# Bidirectional_Voltage_Translator.net
KiCad netlist of a schematic drawn in Altium Designer
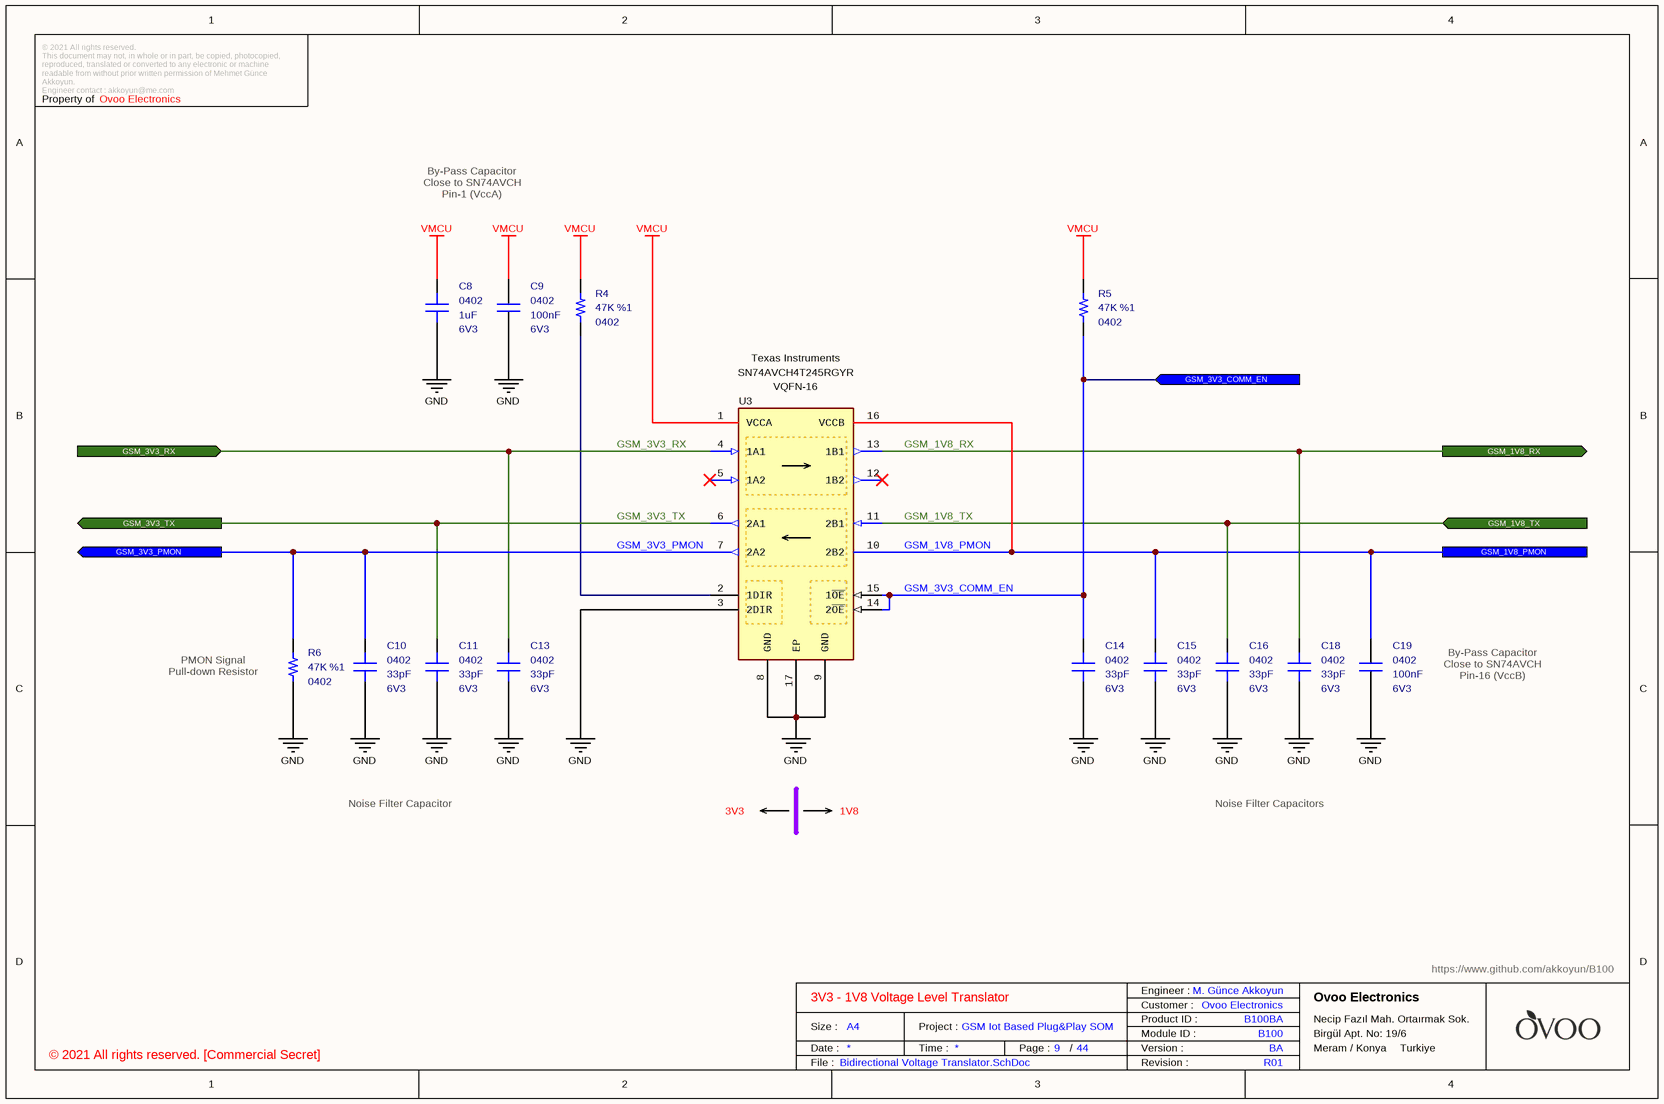
[diagram p0: Bidirectional Voltage Translator.SchDoc]

(export (version "E")
  (design (tool "Eeschema 10.0.6"))
  (components
    (comp (ref "C8")
      (value "1uF")
      (footprint "CAPACITOR_0402")
      (description "Capacitor - 1uF [0402] (Ceramic)")
      (fields
        (field (name "MANUFACTURER_PART_NUMBER") "GRM153R60J105ME95D")
        (field (name "MOUSER_PART_NUMBER") "81-GRM153R60J105ME5D")
        (field (name "CASE") "0402")
        (field (name "VOLTAGE") "6V3")
      )
      (libsource (lib "Ovoo_Schematic") (part "Capacitor - 1uF [0402-6V3)"))
    )
    (comp (ref "C9")
      (value "100nF")
      (footprint "CAPACITOR_0402")
      (description "Capacitor - 100nF [0402-6V3] (Ceramic)")
      (fields
        (field (name "MANUFACTURER_PART_NUMBER") "04026D104KAT4A")
        (field (name "MOUSER_PART_NUMBER") "581-04026D104KAT4A")
        (field (name "CASE") "0402")
        (field (name "VOLTAGE") "6V3")
      )
      (libsource (lib "Ovoo_Schematic") (part "Capacitor - 100nF [0402-6V3]"))
    )
    (comp (ref "C10")
      (value "33pF")
      (footprint "CAPACITOR_0402")
      (description "Capacitor - 33pF [0402] (Ceramic)")
      (fields
        (field (name "MANUFACTURER_PART_NUMBER") "C0402C330J9RACAUTO")
        (field (name "MOUSER_PART_NUMBER") "80-C0402C330J9RAUTO")
        (field (name "CASE") "0402")
        (field (name "VOLTAGE") "6V3")
      )
      (libsource (lib "Ovoo_Schematic") (part "Capacitor - 33pF [0402-6V3]"))
    )
    (comp (ref "C11")
      (value "33pF")
      (footprint "CAPACITOR_0402")
      (description "Capacitor - 33pF [0402] (Ceramic)")
      (fields
        (field (name "MANUFACTURER_PART_NUMBER") "C0402C330J9RACAUTO")
        (field (name "MOUSER_PART_NUMBER") "80-C0402C330J9RAUTO")
        (field (name "CASE") "0402")
        (field (name "VOLTAGE") "6V3")
      )
      (libsource (lib "Ovoo_Schematic") (part "Capacitor - 33pF [0402-6V3]"))
    )
    (comp (ref "C13")
      (value "33pF")
      (footprint "CAPACITOR_0402")
      (description "Capacitor - 33pF [0402] (Ceramic)")
      (fields
        (field (name "MANUFACTURER_PART_NUMBER") "C0402C330J9RACAUTO")
        (field (name "MOUSER_PART_NUMBER") "80-C0402C330J9RAUTO")
        (field (name "CASE") "0402")
        (field (name "VOLTAGE") "6V3")
      )
      (libsource (lib "Ovoo_Schematic") (part "Capacitor - 33pF [0402-6V3]"))
    )
    (comp (ref "C14")
      (value "33pF")
      (footprint "CAPACITOR_0402")
      (description "Capacitor - 33pF [0402] (Ceramic)")
      (fields
        (field (name "MANUFACTURER_PART_NUMBER") "C0402C330J9RACAUTO")
        (field (name "MOUSER_PART_NUMBER") "80-C0402C330J9RAUTO")
        (field (name "CASE") "0402")
        (field (name "VOLTAGE") "6V3")
      )
      (libsource (lib "Ovoo_Schematic") (part "Capacitor - 33pF [0402-6V3]"))
    )
    (comp (ref "C15")
      (value "33pF")
      (footprint "CAPACITOR_0402")
      (description "Capacitor - 33pF [0402] (Ceramic)")
      (fields
        (field (name "MANUFACTURER_PART_NUMBER") "C0402C330J9RACAUTO")
        (field (name "MOUSER_PART_NUMBER") "80-C0402C330J9RAUTO")
        (field (name "CASE") "0402")
        (field (name "VOLTAGE") "6V3")
      )
      (libsource (lib "Ovoo_Schematic") (part "Capacitor - 33pF [0402-6V3]"))
    )
    (comp (ref "C16")
      (value "33pF")
      (footprint "CAPACITOR_0402")
      (description "Capacitor - 33pF [0402] (Ceramic)")
      (fields
        (field (name "MANUFACTURER_PART_NUMBER") "C0402C330J9RACAUTO")
        (field (name "MOUSER_PART_NUMBER") "80-C0402C330J9RAUTO")
        (field (name "CASE") "0402")
        (field (name "VOLTAGE") "6V3")
      )
      (libsource (lib "Ovoo_Schematic") (part "Capacitor - 33pF [0402-6V3]"))
    )
    (comp (ref "C18")
      (value "33pF")
      (footprint "CAPACITOR_0402")
      (description "Capacitor - 33pF [0402] (Ceramic)")
      (fields
        (field (name "MANUFACTURER_PART_NUMBER") "C0402C330J9RACAUTO")
        (field (name "MOUSER_PART_NUMBER") "80-C0402C330J9RAUTO")
        (field (name "CASE") "0402")
        (field (name "VOLTAGE") "6V3")
      )
      (libsource (lib "Ovoo_Schematic") (part "Capacitor - 33pF [0402-6V3]"))
    )
    (comp (ref "C19")
      (value "100nF")
      (footprint "CAPACITOR_0402")
      (description "Capacitor - 100nF [0402-6V3] (Ceramic)")
      (fields
        (field (name "MANUFACTURER_PART_NUMBER") "04026D104KAT4A")
        (field (name "MOUSER_PART_NUMBER") "581-04026D104KAT4A")
        (field (name "CASE") "0402")
        (field (name "VOLTAGE") "6V3")
      )
      (libsource (lib "Ovoo_Schematic") (part "Capacitor - 100nF [0402-6V3]"))
    )
    (comp (ref "R4")
      (value "47K")
      (footprint "RESISTOR_0402")
      (description "Thick Film Resistors - SMD 1/16 W 47 Kohms 1%")
      (fields
        (field (name "MANUFACTURER_PART_NUMBER") "CRCW040247K0FKED")
        (field (name "MOUSER_PART_NUMBER") "71-CRCW0402-47K-E3")
        (field (name "TOLERANCE") "%1")
        (field (name "CASE") "0402")
      )
      (libsource (lib "Ovoo_Schematic") (part "Resistor - 47K"))
    )
    (comp (ref "R5")
      (value "47K")
      (footprint "RESISTOR_0402")
      (description "Thick Film Resistors - SMD 1/16 W 47 Kohms 1%")
      (fields
        (field (name "MANUFACTURER_PART_NUMBER") "CRCW040247K0FKED")
        (field (name "MOUSER_PART_NUMBER") "71-CRCW0402-47K-E3")
        (field (name "TOLERANCE") "%1")
        (field (name "CASE") "0402")
      )
      (libsource (lib "Ovoo_Schematic") (part "Resistor - 47K"))
    )
    (comp (ref "R6")
      (value "47K")
      (footprint "RESISTOR_0402")
      (description "Thick Film Resistors - SMD 1/16 W 47 Kohms 1%")
      (fields
        (field (name "MANUFACTURER_PART_NUMBER") "CRCW040247K0FKED")
        (field (name "MOUSER_PART_NUMBER") "71-CRCW0402-47K-E3")
        (field (name "TOLERANCE") "%1")
        (field (name "CASE") "0402")
      )
      (libsource (lib "Ovoo_Schematic") (part "Resistor - 47K"))
    )
    (comp (ref "U3")
      (value "Voltage Level Shifter")
      (footprint "VQFN16")
      (description "Translation - Voltage Levels Low Power Dual Channel")
      (fields
        (field (name "MOUSER_PART_NUMBER") "595-SN74AVCH4T245RGY")
        (field (name "MANUFACTURER_NAME") "Texas Instruments")
        (field (name "MANUFACTURER PART NUMBER") "SN74AVCH4T245RGYR")
        (field (name "CASE") "VQFN-16")
      )
      (libsource (lib "Ovoo_Schematic") (part "IC - SN74AVCH4T245"))
    )
  )
  (nets
    (net (code "1") (name "/GSM_1V8_PMON") (class "Default")
      (node (ref "C15") (pin "2") (pinfunction "2_2") (pintype "passive"))
      (node (ref "C19") (pin "2") (pinfunction "2_2") (pintype "passive"))
      (node (ref "U3") (pin "10") (pinfunction "2B2_10") (pintype "passive"))
      (node (ref "U3") (pin "16") (pinfunction "VCCB_16") (pintype "power_in"))
    )
    (net (code "2") (name "/GSM_1V8_RX") (class "Default")
      (node (ref "C18") (pin "2") (pinfunction "2_2") (pintype "passive"))
      (node (ref "U3") (pin "13") (pinfunction "1B1_13") (pintype "output"))
    )
    (net (code "3") (name "/GSM_1V8_TX") (class "Default")
      (node (ref "C16") (pin "2") (pinfunction "2_2") (pintype "passive"))
      (node (ref "U3") (pin "11") (pinfunction "2B1_11") (pintype "input"))
    )
    (net (code "4") (name "/GSM_3V3_COMM_EN") (class "Default")
      (node (ref "C14") (pin "2") (pinfunction "2_2") (pintype "passive"))
      (node (ref "R5") (pin "1") (pinfunction "1_1") (pintype "passive"))
      (node (ref "U3") (pin "14") (pinfunction "2~{OE}_14") (pintype "input"))
      (node (ref "U3") (pin "15") (pinfunction "1~{OE}_15") (pintype "input"))
    )
    (net (code "5") (name "/GSM_3V3_PMON") (class "Default")
      (node (ref "C10") (pin "2") (pinfunction "2_2") (pintype "passive"))
      (node (ref "R6") (pin "2") (pinfunction "2_2") (pintype "passive"))
      (node (ref "U3") (pin "7") (pinfunction "2A2_7") (pintype "output"))
    )
    (net (code "6") (name "/GSM_3V3_RX") (class "Default")
      (node (ref "C13") (pin "2") (pinfunction "2_2") (pintype "passive"))
      (node (ref "U3") (pin "4") (pinfunction "1A1_4") (pintype "input"))
    )
    (net (code "7") (name "/GSM_3V3_TX") (class "Default")
      (node (ref "C11") (pin "2") (pinfunction "2_2") (pintype "passive"))
      (node (ref "U3") (pin "6") (pinfunction "2A1_6") (pintype "output"))
    )
    (net (code "8") (name "GND") (class "Default")
      (node (ref "C10") (pin "1") (pinfunction "1_1") (pintype "passive"))
      (node (ref "C11") (pin "1") (pinfunction "1_1") (pintype "passive"))
      (node (ref "C13") (pin "1") (pinfunction "1_1") (pintype "passive"))
      (node (ref "C14") (pin "1") (pinfunction "1_1") (pintype "passive"))
      (node (ref "C15") (pin "1") (pinfunction "1_1") (pintype "passive"))
      (node (ref "C16") (pin "1") (pinfunction "1_1") (pintype "passive"))
      (node (ref "C18") (pin "1") (pinfunction "1_1") (pintype "passive"))
      (node (ref "C19") (pin "1") (pinfunction "1_1") (pintype "passive"))
      (node (ref "C8") (pin "1") (pinfunction "1_1") (pintype "passive"))
      (node (ref "C9") (pin "1") (pinfunction "1_1") (pintype "passive"))
      (node (ref "R6") (pin "1") (pinfunction "1_1") (pintype "passive"))
      (node (ref "U3") (pin "17") (pinfunction "EP_17") (pintype "power_in"))
      (node (ref "U3") (pin "3") (pinfunction "2DIR_3") (pintype "passive"))
      (node (ref "U3") (pin "8") (pinfunction "GND_8") (pintype "power_in"))
      (node (ref "U3") (pin "9") (pinfunction "GND_9") (pintype "power_in"))
    )
    (net (code "9") (name "Net-(U3-1DIR)") (class "Default")
      (node (ref "R4") (pin "1") (pinfunction "1_1") (pintype "passive"))
      (node (ref "U3") (pin "2") (pinfunction "1DIR_2") (pintype "passive"))
    )
    (net (code "10") (name "VMCU") (class "Default")
      (node (ref "C8") (pin "2") (pinfunction "2_2") (pintype "passive"))
      (node (ref "C9") (pin "2") (pinfunction "2_2") (pintype "passive"))
      (node (ref "R4") (pin "2") (pinfunction "2_2") (pintype "passive"))
      (node (ref "R5") (pin "2") (pinfunction "2_2") (pintype "passive"))
      (node (ref "U3") (pin "1") (pinfunction "VCCA_1") (pintype "power_in"))
    )
    (net (code "11") (name "unconnected-(U3-1A2-Pad5)") (class "Default")
      (node (ref "U3") (pin "5") (pinfunction "1A2_5") (pintype "input+no_connect"))
    )
    (net (code "12") (name "unconnected-(U3-1B2-Pad12)") (class "Default")
      (node (ref "U3") (pin "12") (pinfunction "1B2_12") (pintype "output+no_connect"))
    )
  )
)
